# 10.net
KiCad netlist of a schematic drawn in Altium Designer
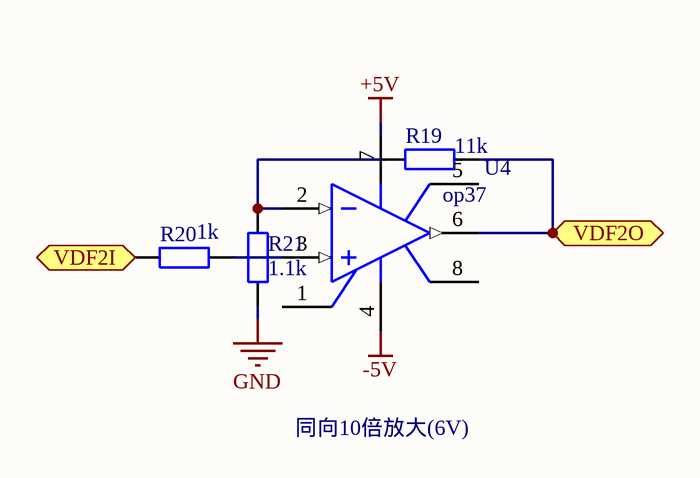
[diagram p0: 同向10倍放大.SchDoc]

(export (version "E")
  (design (tool "Eeschema 10.0.6"))
  (components
    (comp (ref "R19")
      (value "11k")
      (footprint "AXIAL-0.4")
      (description "Resistor")
      (fields (field (name "Comment") "Res2") (field (name "PUBLISHER") "Altium Limited"))
      (libsource (lib "Miscellaneous Devices") (part "Res2"))
    )
    (comp (ref "R20")
      (value "1k")
      (footprint "AXIAL-0.4")
      (description "Resistor")
      (fields (field (name "Comment") "Res2") (field (name "PUBLISHER") "Altium Limited"))
      (libsource (lib "Miscellaneous Devices") (part "Res2"))
    )
    (comp (ref "R21")
      (value "1.1k")
      (footprint "AXIAL-0.4")
      (description "Resistor")
      (fields (field (name "Comment") "Res2") (field (name "PUBLISHER") "Altium Limited"))
      (libsource (lib "") (part "Res2_1"))
    )
    (comp (ref "U4")
      (value "op37")
      (footprint "N-8_A")
      (description "Ultra-Low Offset Voltage Operational Amplifier")
      (fields (field (name "PUBLISHER") "Altium Limited"))
      (libsource (lib "AD Operational Amplifier") (part "ADOP07CN"))
    )
  )
  (nets
    (net (code "1") (name "+5V") (class "Default")
      (node (ref "U4") (pin "7") (pinfunction "V+_7") (pintype "power_in"))
    )
    (net (code "2") (name "-5V") (class "Default")
      (node (ref "U4") (pin "4") (pinfunction "V-_4") (pintype "power_in"))
    )
    (net (code "3") (name "/VDF2I") (class "Default")
      (node (ref "R20") (pin "1") (pinfunction "1_1") (pintype "passive"))
    )
    (net (code "4") (name "/VDF2O") (class "Default")
      (node (ref "R19") (pin "2") (pinfunction "2_2") (pintype "passive"))
      (node (ref "U4") (pin "6") (pinfunction "OUT_6") (pintype "output"))
    )
    (net (code "5") (name "GND") (class "Default")
      (node (ref "R21") (pin "1") (pinfunction "1_1") (pintype "passive"))
    )
    (net (code "6") (name "Net-(U4-IN+)") (class "Default")
      (node (ref "R20") (pin "2") (pinfunction "2_2") (pintype "passive"))
      (node (ref "U4") (pin "3") (pinfunction "IN+_3") (pintype "input"))
    )
    (net (code "7") (name "Net-(U4-IN-)") (class "Default")
      (node (ref "R19") (pin "1") (pinfunction "1_1") (pintype "passive"))
      (node (ref "R21") (pin "2") (pinfunction "2_2") (pintype "passive"))
      (node (ref "U4") (pin "2") (pinfunction "IN-_2") (pintype "input"))
    )
    (net (code "8") (name "unconnected-(U4-NC-Pad5)") (class "Default")
      (node (ref "U4") (pin "5") (pinfunction "NC_5") (pintype "passive"))
    )
    (net (code "9") (name "unconnected-(U4-NULL1-Pad1)") (class "Default")
      (node (ref "U4") (pin "1") (pinfunction "NULL1_1") (pintype "passive"))
    )
    (net (code "10") (name "unconnected-(U4-NULL2-Pad8)") (class "Default")
      (node (ref "U4") (pin "8") (pinfunction "NULL2_8") (pintype "passive"))
    )
  )
)
